# io-pack-3-2.net
KiCad netlist of a schematic drawn in EAGLE
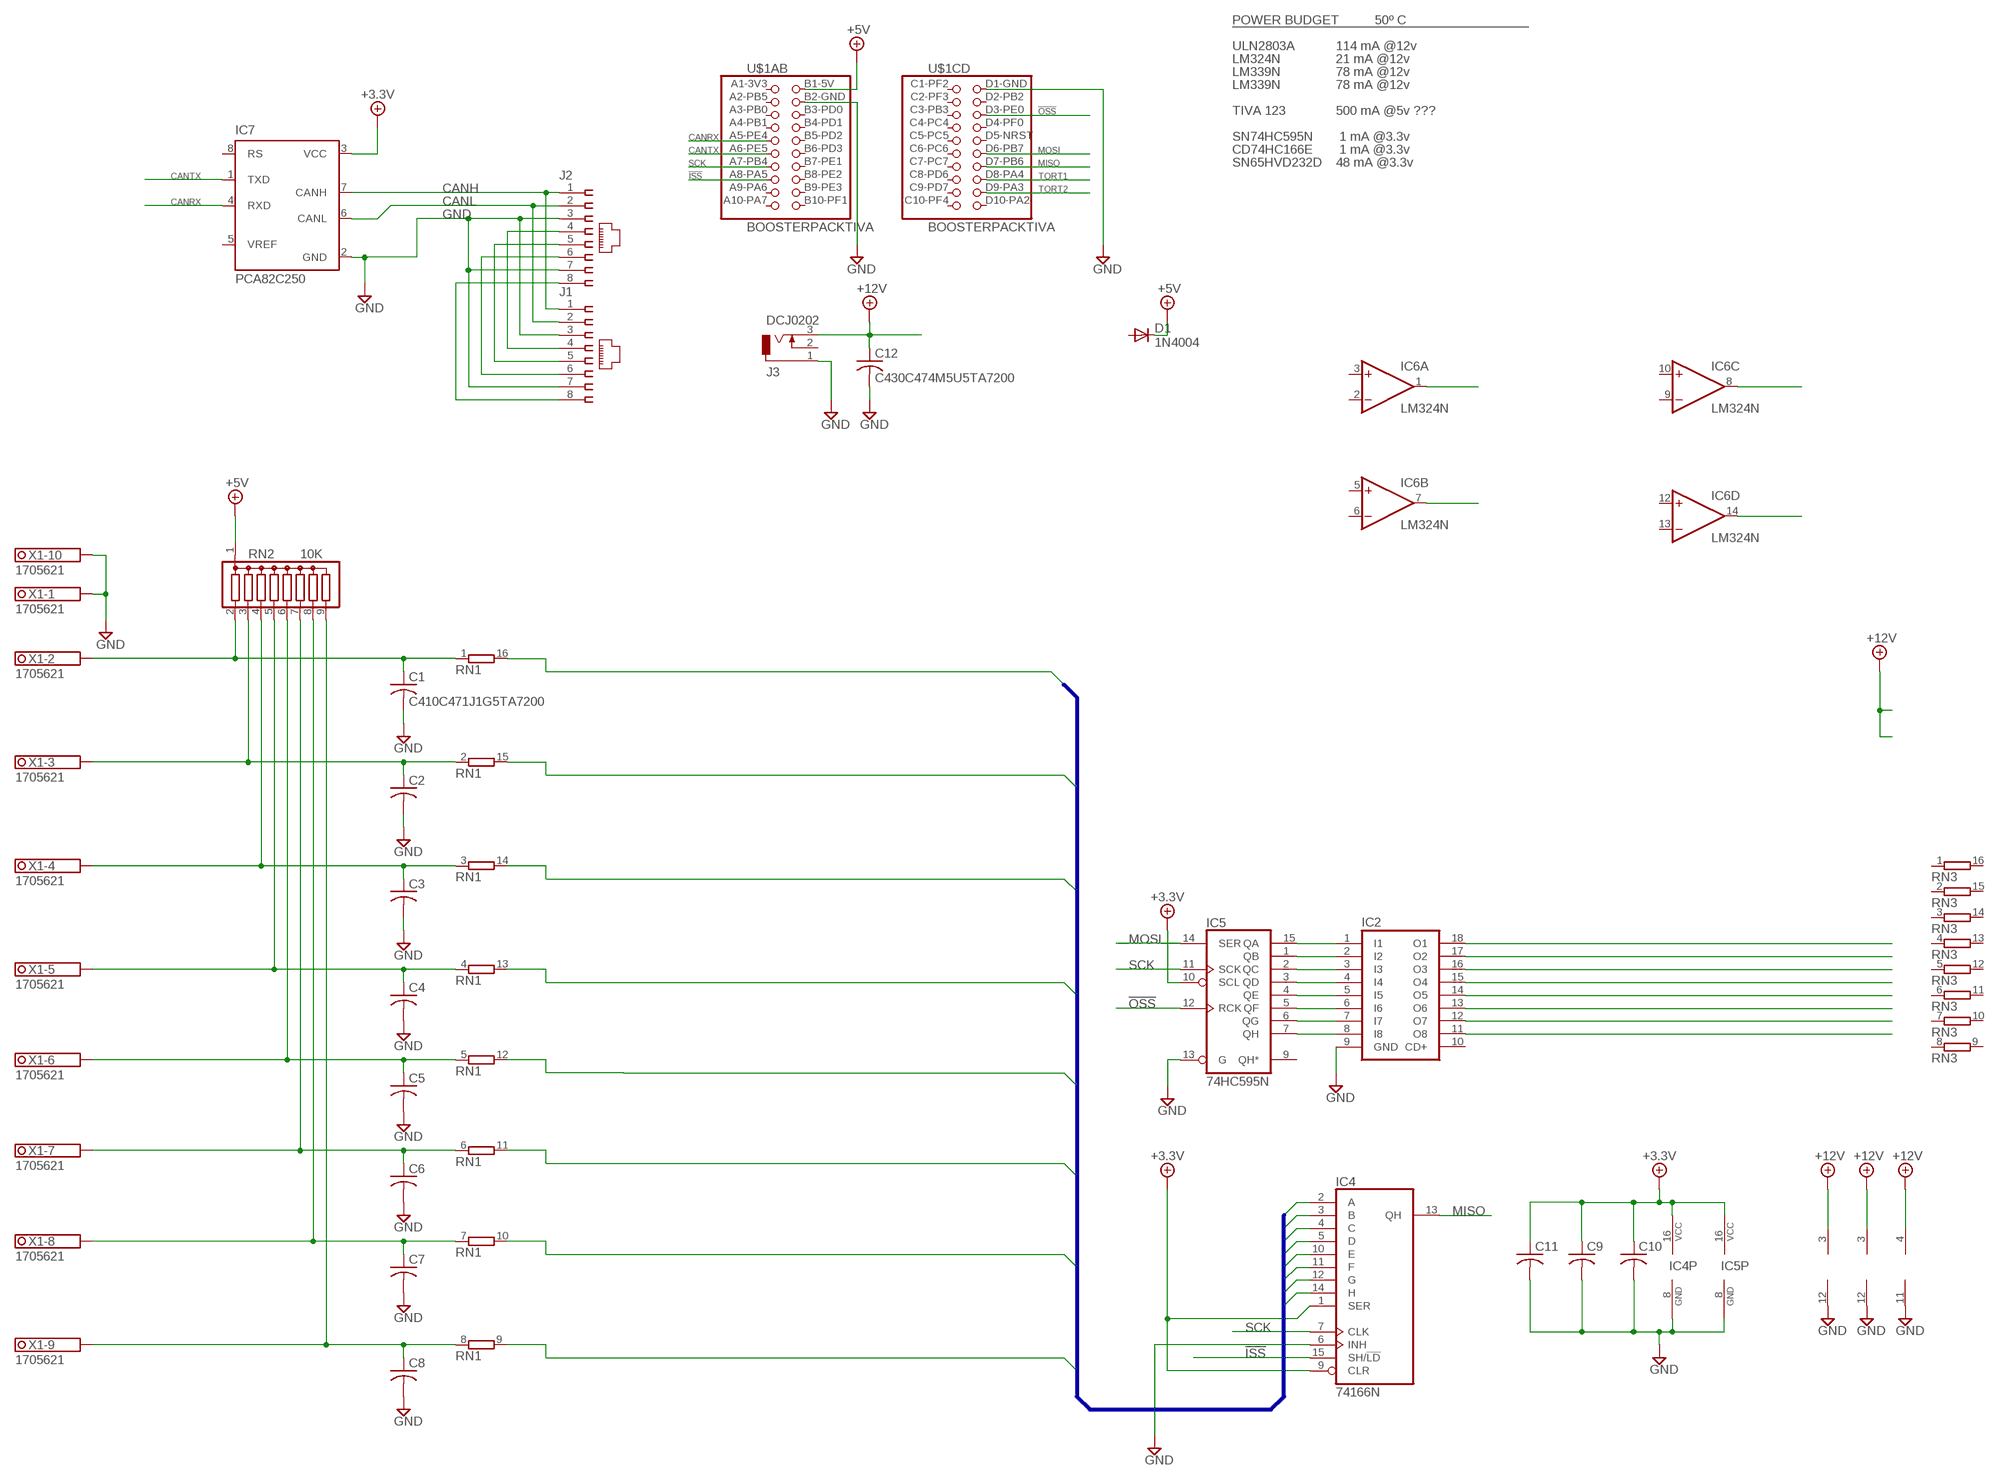
[diagram p0: schematic, sheet 1]

(export (version "E")
  (design (tool "Eeschema 10.0.6"))
  (components
    (comp (ref "C1")
      (value "C410C471J1G5TA7200")
      (footprint "eagle-import:C050-025X075")
      (libsource (lib "eagle-import") (part "C-US050-025X075"))
    )
    (comp (ref "C2")
      (value "C-US050-025X075")
      (footprint "eagle-import:C050-025X075")
      (libsource (lib "eagle-import") (part "C-US050-025X075"))
    )
    (comp (ref "C3")
      (value "C-US050-025X075")
      (footprint "eagle-import:C050-025X075")
      (libsource (lib "eagle-import") (part "C-US050-025X075"))
    )
    (comp (ref "C4")
      (value "C-US050-025X075")
      (footprint "eagle-import:C050-025X075")
      (libsource (lib "eagle-import") (part "C-US050-025X075"))
    )
    (comp (ref "C5")
      (value "C-US050-025X075")
      (footprint "eagle-import:C050-025X075")
      (libsource (lib "eagle-import") (part "C-US050-025X075"))
    )
    (comp (ref "C6")
      (value "C-US050-025X075")
      (footprint "eagle-import:C050-025X075")
      (libsource (lib "eagle-import") (part "C-US050-025X075"))
    )
    (comp (ref "C7")
      (value "C-US050-025X075")
      (footprint "eagle-import:C050-025X075")
      (libsource (lib "eagle-import") (part "C-US050-025X075"))
    )
    (comp (ref "C8")
      (value "C-US050-025X075")
      (footprint "eagle-import:C050-025X075")
      (libsource (lib "eagle-import") (part "C-US050-025X075"))
    )
    (comp (ref "C9")
      (value "C-US050-025X075")
      (footprint "eagle-import:C050-025X075")
      (libsource (lib "eagle-import") (part "C-US050-025X075"))
    )
    (comp (ref "C10")
      (value "C-US050-025X075")
      (footprint "eagle-import:C050-025X075")
      (libsource (lib "eagle-import") (part "C-US050-025X075"))
    )
    (comp (ref "C11")
      (value "C-US050-025X075")
      (footprint "eagle-import:C050-025X075")
      (libsource (lib "eagle-import") (part "C-US050-025X075"))
    )
    (comp (ref "C12")
      (value "C430C474M5U5TA7200")
      (footprint "eagle-import:C075-032X103")
      (libsource (lib "eagle-import") (part "C-US075-032X103"))
    )
    (comp (ref "D1")
      (value "1N4004")
      (footprint "eagle-import:DO41-10")
      (libsource (lib "eagle-import") (part "1N4004"))
    )
    (comp (ref "IC1")
      (value "LM339N")
      (footprint "eagle-import:DIL14")
      (libsource (lib "eagle-import") (part "LM339N"))
    )
    (comp (ref "IC2")
      (value "ULN2803A")
      (footprint "eagle-import:DIL18")
      (libsource (lib "eagle-import") (part "ULN2803A"))
    )
    (comp (ref "IC3")
      (value "LM339N")
      (footprint "eagle-import:DIL14")
      (libsource (lib "eagle-import") (part "LM339N"))
    )
    (comp (ref "IC4")
      (value "74166N")
      (footprint "eagle-import:DIL16")
      (libsource (lib "eagle-import") (part "74166N"))
    )
    (comp (ref "IC5")
      (value "74HC595N")
      (footprint "eagle-import:DIL16")
      (libsource (lib "eagle-import") (part "74595NLS"))
    )
    (comp (ref "IC6")
      (value "LM324N")
      (footprint "eagle-import:DIL14")
      (libsource (lib "eagle-import") (part "LM324N"))
    )
    (comp (ref "IC7")
      (value "PCA82C250")
      (footprint "eagle-import:DIL08")
      (libsource (lib "eagle-import") (part "PCA82C250"))
    )
    (comp (ref "J1")
      (value "555164-1")
      (footprint "eagle-import:555164-1")
      (libsource (lib "eagle-import") (part "555164-1"))
    )
    (comp (ref "J2")
      (value "555164-1")
      (footprint "eagle-import:555164-1")
      (libsource (lib "eagle-import") (part "555164-1"))
    )
    (comp (ref "J3")
      (value "DCJ0202")
      (footprint "eagle-import:DCJ0202")
      (libsource (lib "eagle-import") (part "DCJ0202"))
    )
    (comp (ref "RN1")
      (value "8R-P")
      (footprint "eagle-import:DIL16")
      (libsource (lib "eagle-import") (part "8R-P"))
    )
    (comp (ref "RN2")
      (value "10K")
      (footprint "eagle-import:SIL9")
      (libsource (lib "eagle-import") (part "G08R"))
    )
    (comp (ref "RN3")
      (value "8R-P")
      (footprint "eagle-import:DIL16")
      (libsource (lib "eagle-import") (part "8R-P"))
    )
    (comp (ref "U$1")
      (value "BOOSTERPACKTIVA")
      (footprint "eagle-import:BOOSTERPACK-TIVA")
      (libsource (lib "eagle-import") (part "BOOSTERPACKTIVA"))
    )
    (comp (ref "X1")
      (value "1705621")
      (footprint "eagle-import:1705621")
      (libsource (lib "eagle-import") (part "1705621"))
    )
  )
  (nets
    (net (code "1") (name "+3.3V") (class "Default")
      (node (ref "C10") (pin "1") (pinfunction "1_1") (pintype "passive"))
      (node (ref "C11") (pin "1") (pinfunction "1_1") (pintype "passive"))
      (node (ref "C9") (pin "1") (pinfunction "1_1") (pintype "passive"))
      (node (ref "IC4") (pin "1") (pinfunction "SER_1") (pintype "input"))
      (node (ref "IC4") (pin "16") (pinfunction "VCC_16") (pintype "power_in"))
      (node (ref "IC4") (pin "9") (pinfunction "CLR_9") (pintype "input"))
      (node (ref "IC5") (pin "10") (pinfunction "SCL_10") (pintype "input"))
      (node (ref "IC5") (pin "16") (pinfunction "VCC_16") (pintype "power_in"))
      (node (ref "IC7") (pin "3") (pinfunction "VCC_3") (pintype "power_in"))
    )
    (net (code "2") (name "+5V") (class "Default")
      (node (ref "D1") (pin "C") (pinfunction "C_C") (pintype "passive"))
      (node (ref "RN2") (pin "1") (pinfunction "1_1") (pintype "passive"))
      (node (ref "U$1") (pin "B1-5V") (pinfunction "2_B1-5V") (pintype "passive"))
    )
    (net (code "3") (name "+12V") (class "Default")
      (node (ref "C12") (pin "1") (pinfunction "1_1") (pintype "passive"))
      (node (ref "IC1") (pin "3") (pinfunction "V+_3") (pintype "power_in"))
      (node (ref "IC3") (pin "3") (pinfunction "V+_3") (pintype "power_in"))
      (node (ref "IC6") (pin "4") (pinfunction "V+_4") (pintype "power_in"))
      (node (ref "J3") (pin "3") (pinfunction "3_3") (pintype "passive"))
    )
    (net (code "4") (name "/CANH") (class "Default")
      (node (ref "IC7") (pin "7") (pinfunction "CANH_7") (pintype "bidirectional"))
      (node (ref "J1") (pin "1") (pinfunction "1_1") (pintype "passive"))
      (node (ref "J2") (pin "1") (pinfunction "1_1") (pintype "passive"))
    )
    (net (code "5") (name "/CANL") (class "Default")
      (node (ref "IC7") (pin "6") (pinfunction "CANL_6") (pintype "bidirectional"))
      (node (ref "J1") (pin "2") (pinfunction "2_2") (pintype "passive"))
      (node (ref "J2") (pin "2") (pinfunction "2_2") (pintype "passive"))
    )
    (net (code "6") (name "/CANRX") (class "Default")
      (node (ref "IC7") (pin "4") (pinfunction "RXD_4") (pintype "output"))
      (node (ref "U$1") (pin "A5-PE4") (pinfunction "9_A5-PE4") (pintype "passive"))
    )
    (net (code "7") (name "/CANTX") (class "Default")
      (node (ref "IC7") (pin "1") (pinfunction "TXD_1") (pintype "input"))
      (node (ref "U$1") (pin "A6-PE5") (pinfunction "11_A6-PE5") (pintype "passive"))
    )
    (net (code "8") (name "/IN0") (class "Default")
      (node (ref "IC4") (pin "2") (pinfunction "A_2") (pintype "input"))
      (node (ref "RN1") (pin "16") (pinfunction "2_16") (pintype "passive"))
    )
    (net (code "9") (name "/IN1") (class "Default")
      (node (ref "IC4") (pin "3") (pinfunction "B_3") (pintype "input"))
      (node (ref "RN1") (pin "15") (pinfunction "2_15") (pintype "passive"))
    )
    (net (code "10") (name "/IN2") (class "Default")
      (node (ref "IC4") (pin "4") (pinfunction "C_4") (pintype "input"))
      (node (ref "RN1") (pin "14") (pinfunction "2_14") (pintype "passive"))
    )
    (net (code "11") (name "/IN3") (class "Default")
      (node (ref "IC4") (pin "5") (pinfunction "D_5") (pintype "input"))
      (node (ref "RN1") (pin "13") (pinfunction "2_13") (pintype "passive"))
    )
    (net (code "12") (name "/IN4") (class "Default")
      (node (ref "IC4") (pin "10") (pinfunction "E_10") (pintype "input"))
      (node (ref "RN1") (pin "12") (pinfunction "2_12") (pintype "passive"))
    )
    (net (code "13") (name "/IN5") (class "Default")
      (node (ref "IC4") (pin "11") (pinfunction "F_11") (pintype "input"))
      (node (ref "RN1") (pin "11") (pinfunction "2_11") (pintype "passive"))
    )
    (net (code "14") (name "/IN6") (class "Default")
      (node (ref "IC4") (pin "12") (pinfunction "G_12") (pintype "input"))
      (node (ref "RN1") (pin "10") (pinfunction "2_10") (pintype "passive"))
    )
    (net (code "15") (name "/IN7") (class "Default")
      (node (ref "IC4") (pin "14") (pinfunction "H_14") (pintype "input"))
      (node (ref "RN1") (pin "9") (pinfunction "2_9") (pintype "passive"))
    )
    (net (code "16") (name "/MISO") (class "Default")
      (node (ref "IC4") (pin "13") (pinfunction "QH_13") (pintype "output"))
      (node (ref "U$1") (pin "D7-PB6") (pinfunction "14_D7-PB6") (pintype "passive"))
    )
    (net (code "17") (name "/MOSI") (class "Default")
      (node (ref "IC5") (pin "14") (pinfunction "SER_14") (pintype "input"))
      (node (ref "U$1") (pin "D6-PB7") (pinfunction "12_D6-PB7") (pintype "passive"))
    )
    (net (code "18") (name "/SCK") (class "Default")
      (node (ref "IC4") (pin "7") (pinfunction "CLK_7") (pintype "input"))
      (node (ref "IC5") (pin "11") (pinfunction "SCK_11") (pintype "input"))
      (node (ref "U$1") (pin "A7-PB4") (pinfunction "13_A7-PB4") (pintype "passive"))
    )
    (net (code "19") (name "/TORT1") (class "Default")
      (node (ref "U$1") (pin "D8-PA4") (pinfunction "16_D8-PA4") (pintype "passive"))
    )
    (net (code "20") (name "/TORT2") (class "Default")
      (node (ref "U$1") (pin "D9-PA3") (pinfunction "18_D9-PA3") (pintype "passive"))
    )
    (net (code "21") (name "/~{ISS}") (class "Default")
      (node (ref "IC4") (pin "15") (pinfunction "SH/~{LD}_15") (pintype "input"))
      (node (ref "U$1") (pin "A8-PA5") (pinfunction "15_A8-PA5") (pintype "passive"))
    )
    (net (code "22") (name "/~{OSS}") (class "Default")
      (node (ref "IC5") (pin "12") (pinfunction "RCK_12") (pintype "input"))
      (node (ref "U$1") (pin "D3-PE0") (pinfunction "6_D3-PE0") (pintype "passive"))
    )
    (net (code "23") (name "GND") (class "Default")
      (node (ref "C1") (pin "2") (pinfunction "2_2") (pintype "passive"))
      (node (ref "C10") (pin "2") (pinfunction "2_2") (pintype "passive"))
      (node (ref "C11") (pin "2") (pinfunction "2_2") (pintype "passive"))
      (node (ref "C12") (pin "2") (pinfunction "2_2") (pintype "passive"))
      (node (ref "C2") (pin "2") (pinfunction "2_2") (pintype "passive"))
      (node (ref "C3") (pin "2") (pinfunction "2_2") (pintype "passive"))
      (node (ref "C4") (pin "2") (pinfunction "2_2") (pintype "passive"))
      (node (ref "C5") (pin "2") (pinfunction "2_2") (pintype "passive"))
      (node (ref "C6") (pin "2") (pinfunction "2_2") (pintype "passive"))
      (node (ref "C7") (pin "2") (pinfunction "2_2") (pintype "passive"))
      (node (ref "C8") (pin "2") (pinfunction "2_2") (pintype "passive"))
      (node (ref "C9") (pin "2") (pinfunction "2_2") (pintype "passive"))
      (node (ref "IC1") (pin "12") (pinfunction "GND_12") (pintype "power_in"))
      (node (ref "IC2") (pin "9") (pinfunction "GND_9") (pintype "power_in"))
      (node (ref "IC3") (pin "12") (pinfunction "GND_12") (pintype "power_in"))
      (node (ref "IC4") (pin "6") (pinfunction "INH_6") (pintype "input"))
      (node (ref "IC4") (pin "8") (pinfunction "GND_8") (pintype "power_in"))
      (node (ref "IC5") (pin "13") (pinfunction "G_13") (pintype "input"))
      (node (ref "IC5") (pin "8") (pinfunction "GND_8") (pintype "power_in"))
      (node (ref "IC6") (pin "11") (pinfunction "V-_11") (pintype "power_in"))
      (node (ref "IC7") (pin "2") (pinfunction "GND_2") (pintype "power_in"))
      (node (ref "J1") (pin "3") (pinfunction "3_3") (pintype "passive"))
      (node (ref "J1") (pin "7") (pinfunction "7_7") (pintype "passive"))
      (node (ref "J2") (pin "3") (pinfunction "3_3") (pintype "passive"))
      (node (ref "J2") (pin "7") (pinfunction "7_7") (pintype "passive"))
      (node (ref "J3") (pin "1") (pinfunction "1_1") (pintype "passive"))
      (node (ref "U$1") (pin "B2-GND") (pinfunction "4_B2-GND") (pintype "passive"))
      (node (ref "U$1") (pin "D1-GND") (pinfunction "2_D1-GND") (pintype "passive"))
      (node (ref "X1") (pin "1.1") (pinfunction "1A_1.1") (pintype "passive"))
      (node (ref "X1") (pin "1.2") (pinfunction "1A_1.2") (pintype "passive"))
      (node (ref "X1") (pin "10.1") (pinfunction "1A_10.1") (pintype "passive"))
      (node (ref "X1") (pin "10.2") (pinfunction "1A_10.2") (pintype "passive"))
    )
    (net (code "24") (name "Net-(C1-Pad1)") (class "Default")
      (node (ref "C1") (pin "1") (pinfunction "1_1") (pintype "passive"))
      (node (ref "RN1") (pin "1") (pinfunction "1_1") (pintype "passive"))
      (node (ref "RN2") (pin "2") (pinfunction "2_2") (pintype "passive"))
      (node (ref "X1") (pin "2.1") (pinfunction "1A_2.1") (pintype "passive"))
      (node (ref "X1") (pin "2.2") (pinfunction "1A_2.2") (pintype "passive"))
    )
    (net (code "25") (name "Net-(IC2-I1)") (class "Default")
      (node (ref "IC2") (pin "1") (pinfunction "I1_1") (pintype "input"))
      (node (ref "IC5") (pin "15") (pinfunction "QA_15") (pintype "tri_state"))
    )
    (net (code "26") (name "Net-(IC2-I2)") (class "Default")
      (node (ref "IC2") (pin "2") (pinfunction "I2_2") (pintype "input"))
      (node (ref "IC5") (pin "1") (pinfunction "QB_1") (pintype "tri_state"))
    )
    (net (code "27") (name "Net-(IC2-I3)") (class "Default")
      (node (ref "IC2") (pin "3") (pinfunction "I3_3") (pintype "input"))
      (node (ref "IC5") (pin "2") (pinfunction "QC_2") (pintype "tri_state"))
    )
    (net (code "28") (name "Net-(IC2-I4)") (class "Default")
      (node (ref "IC2") (pin "4") (pinfunction "I4_4") (pintype "input"))
      (node (ref "IC5") (pin "3") (pinfunction "QD_3") (pintype "tri_state"))
    )
    (net (code "29") (name "Net-(IC2-I5)") (class "Default")
      (node (ref "IC2") (pin "5") (pinfunction "I5_5") (pintype "input"))
      (node (ref "IC5") (pin "4") (pinfunction "QE_4") (pintype "tri_state"))
    )
    (net (code "30") (name "Net-(IC2-I6)") (class "Default")
      (node (ref "IC2") (pin "6") (pinfunction "I6_6") (pintype "input"))
      (node (ref "IC5") (pin "5") (pinfunction "QF_5") (pintype "tri_state"))
    )
    (net (code "31") (name "Net-(IC2-I7)") (class "Default")
      (node (ref "IC2") (pin "7") (pinfunction "I7_7") (pintype "input"))
      (node (ref "IC5") (pin "6") (pinfunction "QG_6") (pintype "tri_state"))
    )
    (net (code "32") (name "Net-(IC2-I8)") (class "Default")
      (node (ref "IC2") (pin "8") (pinfunction "I8_8") (pintype "input"))
      (node (ref "IC5") (pin "7") (pinfunction "QH_7") (pintype "tri_state"))
    )
    (net (code "33") (name "Net-(J1-Pad4)") (class "Default")
      (node (ref "J1") (pin "4") (pinfunction "4_4") (pintype "passive"))
      (node (ref "J2") (pin "4") (pinfunction "4_4") (pintype "passive"))
    )
    (net (code "34") (name "Net-(J1-Pad5)") (class "Default")
      (node (ref "J1") (pin "5") (pinfunction "5_5") (pintype "passive"))
      (node (ref "J2") (pin "5") (pinfunction "5_5") (pintype "passive"))
    )
    (net (code "35") (name "Net-(J1-Pad6)") (class "Default")
      (node (ref "J1") (pin "6") (pinfunction "6_6") (pintype "passive"))
      (node (ref "J2") (pin "6") (pinfunction "6_6") (pintype "passive"))
    )
    (net (code "36") (name "Net-(J1-Pad8)") (class "Default")
      (node (ref "J1") (pin "8") (pinfunction "8_8") (pintype "passive"))
      (node (ref "J2") (pin "8") (pinfunction "8_8") (pintype "passive"))
    )
    (net (code "37") (name "Net-(RN1B-1)") (class "Default")
      (node (ref "C2") (pin "1") (pinfunction "1_1") (pintype "passive"))
      (node (ref "RN1") (pin "2") (pinfunction "1_2") (pintype "passive"))
      (node (ref "RN2") (pin "3") (pinfunction "3_3") (pintype "passive"))
      (node (ref "X1") (pin "3.1") (pinfunction "1A_3.1") (pintype "passive"))
      (node (ref "X1") (pin "3.2") (pinfunction "1A_3.2") (pintype "passive"))
    )
    (net (code "38") (name "Net-(RN1C-1)") (class "Default")
      (node (ref "C3") (pin "1") (pinfunction "1_1") (pintype "passive"))
      (node (ref "RN1") (pin "3") (pinfunction "1_3") (pintype "passive"))
      (node (ref "RN2") (pin "4") (pinfunction "4_4") (pintype "passive"))
      (node (ref "X1") (pin "4.1") (pinfunction "1A_4.1") (pintype "passive"))
      (node (ref "X1") (pin "4.2") (pinfunction "1A_4.2") (pintype "passive"))
    )
    (net (code "39") (name "Net-(RN1D-1)") (class "Default")
      (node (ref "C4") (pin "1") (pinfunction "1_1") (pintype "passive"))
      (node (ref "RN1") (pin "4") (pinfunction "1_4") (pintype "passive"))
      (node (ref "RN2") (pin "5") (pinfunction "5_5") (pintype "passive"))
      (node (ref "X1") (pin "5.1") (pinfunction "1A_5.1") (pintype "passive"))
      (node (ref "X1") (pin "5.2") (pinfunction "1A_5.2") (pintype "passive"))
    )
    (net (code "40") (name "Net-(RN1E-1)") (class "Default")
      (node (ref "C5") (pin "1") (pinfunction "1_1") (pintype "passive"))
      (node (ref "RN1") (pin "5") (pinfunction "1_5") (pintype "passive"))
      (node (ref "RN2") (pin "6") (pinfunction "6_6") (pintype "passive"))
      (node (ref "X1") (pin "6.1") (pinfunction "1A_6.1") (pintype "passive"))
      (node (ref "X1") (pin "6.2") (pinfunction "1A_6.2") (pintype "passive"))
    )
    (net (code "41") (name "Net-(RN1F-1)") (class "Default")
      (node (ref "C6") (pin "1") (pinfunction "1_1") (pintype "passive"))
      (node (ref "RN1") (pin "6") (pinfunction "1_6") (pintype "passive"))
      (node (ref "RN2") (pin "7") (pinfunction "7_7") (pintype "passive"))
      (node (ref "X1") (pin "7.1") (pinfunction "1A_7.1") (pintype "passive"))
      (node (ref "X1") (pin "7.2") (pinfunction "1A_7.2") (pintype "passive"))
    )
    (net (code "42") (name "Net-(RN1G-1)") (class "Default")
      (node (ref "C7") (pin "1") (pinfunction "1_1") (pintype "passive"))
      (node (ref "RN1") (pin "7") (pinfunction "1_7") (pintype "passive"))
      (node (ref "RN2") (pin "8") (pinfunction "8_8") (pintype "passive"))
      (node (ref "X1") (pin "8.1") (pinfunction "1A_8.1") (pintype "passive"))
      (node (ref "X1") (pin "8.2") (pinfunction "1A_8.2") (pintype "passive"))
    )
    (net (code "43") (name "Net-(RN1H-1)") (class "Default")
      (node (ref "C8") (pin "1") (pinfunction "1_1") (pintype "passive"))
      (node (ref "RN1") (pin "8") (pinfunction "1_8") (pintype "passive"))
      (node (ref "RN2") (pin "9") (pinfunction "9_9") (pintype "passive"))
      (node (ref "X1") (pin "9.1") (pinfunction "1A_9.1") (pintype "passive"))
      (node (ref "X1") (pin "9.2") (pinfunction "1A_9.2") (pintype "passive"))
    )
    (net (code "44") (name "unconnected-(D1-PadA)") (class "Default")
      (node (ref "D1") (pin "A") (pinfunction "A_A") (pintype "passive"))
    )
    (net (code "45") (name "unconnected-(IC2-CD+-Pad10)") (class "Default")
      (node (ref "IC2") (pin "10") (pinfunction "CD+_10") (pintype "passive"))
    )
    (net (code "46") (name "unconnected-(IC2-O1-Pad18)") (class "Default")
      (node (ref "IC2") (pin "18") (pinfunction "O1_18") (pintype "open_collector"))
    )
    (net (code "47") (name "unconnected-(IC2-O2-Pad17)") (class "Default")
      (node (ref "IC2") (pin "17") (pinfunction "O2_17") (pintype "open_collector"))
    )
    (net (code "48") (name "unconnected-(IC2-O3-Pad16)") (class "Default")
      (node (ref "IC2") (pin "16") (pinfunction "O3_16") (pintype "open_collector"))
    )
    (net (code "49") (name "unconnected-(IC2-O4-Pad15)") (class "Default")
      (node (ref "IC2") (pin "15") (pinfunction "O4_15") (pintype "open_collector"))
    )
    (net (code "50") (name "unconnected-(IC2-O5-Pad14)") (class "Default")
      (node (ref "IC2") (pin "14") (pinfunction "O5_14") (pintype "open_collector"))
    )
    (net (code "51") (name "unconnected-(IC2-O6-Pad13)") (class "Default")
      (node (ref "IC2") (pin "13") (pinfunction "O6_13") (pintype "open_collector"))
    )
    (net (code "52") (name "unconnected-(IC2-O7-Pad12)") (class "Default")
      (node (ref "IC2") (pin "12") (pinfunction "O7_12") (pintype "open_collector"))
    )
    (net (code "53") (name "unconnected-(IC2-O8-Pad11)") (class "Default")
      (node (ref "IC2") (pin "11") (pinfunction "O8_11") (pintype "open_collector"))
    )
    (net (code "54") (name "unconnected-(IC5A-QH*-Pad9)") (class "Default")
      (node (ref "IC5") (pin "9") (pinfunction "QH*_9") (pintype "tri_state"))
    )
    (net (code "55") (name "unconnected-(IC6A-+IN-Pad3)") (class "Default")
      (node (ref "IC6") (pin "3") (pinfunction "+IN_3") (pintype "input"))
    )
    (net (code "56") (name "unconnected-(IC6A--IN-Pad2)") (class "Default")
      (node (ref "IC6") (pin "2") (pinfunction "-IN_2") (pintype "input"))
    )
    (net (code "57") (name "unconnected-(IC6A-OUT-Pad1)") (class "Default")
      (node (ref "IC6") (pin "1") (pinfunction "OUT_1") (pintype "output"))
    )
    (net (code "58") (name "unconnected-(IC6B-+IN-Pad5)") (class "Default")
      (node (ref "IC6") (pin "5") (pinfunction "+IN_5") (pintype "input"))
    )
    (net (code "59") (name "unconnected-(IC6B--IN-Pad6)") (class "Default")
      (node (ref "IC6") (pin "6") (pinfunction "-IN_6") (pintype "input"))
    )
    (net (code "60") (name "unconnected-(IC6B-OUT-Pad7)") (class "Default")
      (node (ref "IC6") (pin "7") (pinfunction "OUT_7") (pintype "output"))
    )
    (net (code "61") (name "unconnected-(IC6C-+IN-Pad10)") (class "Default")
      (node (ref "IC6") (pin "10") (pinfunction "+IN_10") (pintype "input"))
    )
    (net (code "62") (name "unconnected-(IC6C--IN-Pad9)") (class "Default")
      (node (ref "IC6") (pin "9") (pinfunction "-IN_9") (pintype "input"))
    )
    (net (code "63") (name "unconnected-(IC6C-OUT-Pad8)") (class "Default")
      (node (ref "IC6") (pin "8") (pinfunction "OUT_8") (pintype "output"))
    )
    (net (code "64") (name "unconnected-(IC6D-+IN-Pad12)") (class "Default")
      (node (ref "IC6") (pin "12") (pinfunction "+IN_12") (pintype "input"))
    )
    (net (code "65") (name "unconnected-(IC6D--IN-Pad13)") (class "Default")
      (node (ref "IC6") (pin "13") (pinfunction "-IN_13") (pintype "input"))
    )
    (net (code "66") (name "unconnected-(IC6D-OUT-Pad14)") (class "Default")
      (node (ref "IC6") (pin "14") (pinfunction "OUT_14") (pintype "output"))
    )
    (net (code "67") (name "unconnected-(IC7-RS-Pad8)") (class "Default")
      (node (ref "IC7") (pin "8") (pinfunction "RS_8") (pintype "input"))
    )
    (net (code "68") (name "unconnected-(IC7-VREF-Pad5)") (class "Default")
      (node (ref "IC7") (pin "5") (pinfunction "VREF_5") (pintype "output"))
    )
    (net (code "69") (name "unconnected-(J3-Pad2)") (class "Default")
      (node (ref "J3") (pin "2") (pinfunction "2_2") (pintype "passive"))
    )
    (net (code "70") (name "unconnected-(RN3-Pad1)") (class "Default")
      (node (ref "RN3") (pin "1") (pinfunction "1_1") (pintype "passive"))
    )
    (net (code "71") (name "unconnected-(RN3A-2-Pad16)") (class "Default")
      (node (ref "RN3") (pin "16") (pinfunction "2_16") (pintype "passive"))
    )
    (net (code "72") (name "unconnected-(RN3B-1-Pad2)") (class "Default")
      (node (ref "RN3") (pin "2") (pinfunction "1_2") (pintype "passive"))
    )
    (net (code "73") (name "unconnected-(RN3B-2-Pad15)") (class "Default")
      (node (ref "RN3") (pin "15") (pinfunction "2_15") (pintype "passive"))
    )
    (net (code "74") (name "unconnected-(RN3C-1-Pad3)") (class "Default")
      (node (ref "RN3") (pin "3") (pinfunction "1_3") (pintype "passive"))
    )
    (net (code "75") (name "unconnected-(RN3C-2-Pad14)") (class "Default")
      (node (ref "RN3") (pin "14") (pinfunction "2_14") (pintype "passive"))
    )
    (net (code "76") (name "unconnected-(RN3D-1-Pad4)") (class "Default")
      (node (ref "RN3") (pin "4") (pinfunction "1_4") (pintype "passive"))
    )
    (net (code "77") (name "unconnected-(RN3D-2-Pad13)") (class "Default")
      (node (ref "RN3") (pin "13") (pinfunction "2_13") (pintype "passive"))
    )
    (net (code "78") (name "unconnected-(RN3E-1-Pad5)") (class "Default")
      (node (ref "RN3") (pin "5") (pinfunction "1_5") (pintype "passive"))
    )
    (net (code "79") (name "unconnected-(RN3E-2-Pad12)") (class "Default")
      (node (ref "RN3") (pin "12") (pinfunction "2_12") (pintype "passive"))
    )
    (net (code "80") (name "unconnected-(RN3F-1-Pad6)") (class "Default")
      (node (ref "RN3") (pin "6") (pinfunction "1_6") (pintype "passive"))
    )
    (net (code "81") (name "unconnected-(RN3F-2-Pad11)") (class "Default")
      (node (ref "RN3") (pin "11") (pinfunction "2_11") (pintype "passive"))
    )
    (net (code "82") (name "unconnected-(RN3G-1-Pad7)") (class "Default")
      (node (ref "RN3") (pin "7") (pinfunction "1_7") (pintype "passive"))
    )
    (net (code "83") (name "unconnected-(RN3G-2-Pad10)") (class "Default")
      (node (ref "RN3") (pin "10") (pinfunction "2_10") (pintype "passive"))
    )
    (net (code "84") (name "unconnected-(RN3H-1-Pad8)") (class "Default")
      (node (ref "RN3") (pin "8") (pinfunction "1_8") (pintype "passive"))
    )
    (net (code "85") (name "unconnected-(RN3H-2-Pad9)") (class "Default")
      (node (ref "RN3") (pin "9") (pinfunction "2_9") (pintype "passive"))
    )
    (net (code "86") (name "unconnected-(U$1A-1-PadA1-3V3)") (class "Default")
      (node (ref "U$1") (pin "A1-3V3") (pinfunction "1_A1-3V3") (pintype "passive"))
    )
    (net (code "87") (name "unconnected-(U$1A-3-PadA2-PB5)") (class "Default")
      (node (ref "U$1") (pin "A2-PB5") (pinfunction "3_A2-PB5") (pintype "passive"))
    )
    (net (code "88") (name "unconnected-(U$1A-5-PadA3-PB0)") (class "Default")
      (node (ref "U$1") (pin "A3-PB0") (pinfunction "5_A3-PB0") (pintype "passive"))
    )
    (net (code "89") (name "unconnected-(U$1A-6-PadB3-PD0)") (class "Default")
      (node (ref "U$1") (pin "B3-PD0") (pinfunction "6_B3-PD0") (pintype "passive"))
    )
    (net (code "90") (name "unconnected-(U$1A-7-PadA4-PB1)") (class "Default")
      (node (ref "U$1") (pin "A4-PB1") (pinfunction "7_A4-PB1") (pintype "passive"))
    )
    (net (code "91") (name "unconnected-(U$1A-8-PadB4-PD1)") (class "Default")
      (node (ref "U$1") (pin "B4-PD1") (pinfunction "8_B4-PD1") (pintype "passive"))
    )
    (net (code "92") (name "unconnected-(U$1A-10-PadB5-PD2)") (class "Default")
      (node (ref "U$1") (pin "B5-PD2") (pinfunction "10_B5-PD2") (pintype "passive"))
    )
    (net (code "93") (name "unconnected-(U$1A-12-PadB6-PD3)") (class "Default")
      (node (ref "U$1") (pin "B6-PD3") (pinfunction "12_B6-PD3") (pintype "passive"))
    )
    (net (code "94") (name "unconnected-(U$1A-14-PadB7-PE1)") (class "Default")
      (node (ref "U$1") (pin "B7-PE1") (pinfunction "14_B7-PE1") (pintype "passive"))
    )
    (net (code "95") (name "unconnected-(U$1A-16-PadB8-PE2)") (class "Default")
      (node (ref "U$1") (pin "B8-PE2") (pinfunction "16_B8-PE2") (pintype "passive"))
    )
    (net (code "96") (name "unconnected-(U$1A-17-PadA9-PA6)") (class "Default")
      (node (ref "U$1") (pin "A9-PA6") (pinfunction "17_A9-PA6") (pintype "passive"))
    )
    (net (code "97") (name "unconnected-(U$1A-18-PadB9-PE3)") (class "Default")
      (node (ref "U$1") (pin "B9-PE3") (pinfunction "18_B9-PE3") (pintype "passive"))
    )
    (net (code "98") (name "unconnected-(U$1A-19-PadA10-PA7)") (class "Default")
      (node (ref "U$1") (pin "A10-PA7") (pinfunction "19_A10-PA7") (pintype "passive"))
    )
    (net (code "99") (name "unconnected-(U$1A-20-PadB10-PF1)") (class "Default")
      (node (ref "U$1") (pin "B10-PF1") (pinfunction "20_B10-PF1") (pintype "passive"))
    )
    (net (code "100") (name "unconnected-(U$1B-1-PadC1-PF2)") (class "Default")
      (node (ref "U$1") (pin "C1-PF2") (pinfunction "1_C1-PF2") (pintype "passive"))
    )
    (net (code "101") (name "unconnected-(U$1B-3-PadC2-PF3)") (class "Default")
      (node (ref "U$1") (pin "C2-PF3") (pinfunction "3_C2-PF3") (pintype "passive"))
    )
    (net (code "102") (name "unconnected-(U$1B-4-PadD2-PB2)") (class "Default")
      (node (ref "U$1") (pin "D2-PB2") (pinfunction "4_D2-PB2") (pintype "passive"))
    )
    (net (code "103") (name "unconnected-(U$1B-5-PadC3-PB3)") (class "Default")
      (node (ref "U$1") (pin "C3-PB3") (pinfunction "5_C3-PB3") (pintype "passive"))
    )
    (net (code "104") (name "unconnected-(U$1B-7-PadC4-PC4)") (class "Default")
      (node (ref "U$1") (pin "C4-PC4") (pinfunction "7_C4-PC4") (pintype "passive"))
    )
    (net (code "105") (name "unconnected-(U$1B-8-PadD4-PF0)") (class "Default")
      (node (ref "U$1") (pin "D4-PF0") (pinfunction "8_D4-PF0") (pintype "passive"))
    )
    (net (code "106") (name "unconnected-(U$1B-9-PadC5-PC5)") (class "Default")
      (node (ref "U$1") (pin "C5-PC5") (pinfunction "9_C5-PC5") (pintype "passive"))
    )
    (net (code "107") (name "unconnected-(U$1B-10-PadD5-NRST)") (class "Default")
      (node (ref "U$1") (pin "D5-NRST") (pinfunction "10_D5-NRST") (pintype "passive"))
    )
    (net (code "108") (name "unconnected-(U$1B-11-PadC6-PC6)") (class "Default")
      (node (ref "U$1") (pin "C6-PC6") (pinfunction "11_C6-PC6") (pintype "passive"))
    )
    (net (code "109") (name "unconnected-(U$1B-13-PadC7-PC7)") (class "Default")
      (node (ref "U$1") (pin "C7-PC7") (pinfunction "13_C7-PC7") (pintype "passive"))
    )
    (net (code "110") (name "unconnected-(U$1B-15-PadC8-PD6)") (class "Default")
      (node (ref "U$1") (pin "C8-PD6") (pinfunction "15_C8-PD6") (pintype "passive"))
    )
    (net (code "111") (name "unconnected-(U$1B-17-PadC9-PD7)") (class "Default")
      (node (ref "U$1") (pin "C9-PD7") (pinfunction "17_C9-PD7") (pintype "passive"))
    )
    (net (code "112") (name "unconnected-(U$1B-19-PadC10-PF4)") (class "Default")
      (node (ref "U$1") (pin "C10-PF4") (pinfunction "19_C10-PF4") (pintype "passive"))
    )
    (net (code "113") (name "unconnected-(U$1B-20-PadD10-PA2)") (class "Default")
      (node (ref "U$1") (pin "D10-PA2") (pinfunction "20_D10-PA2") (pintype "passive"))
    )
  )
)
